# SMD_cree_driver_led-mosfet002_dem.net
KiCad netlist of a schematic drawn in EAGLE
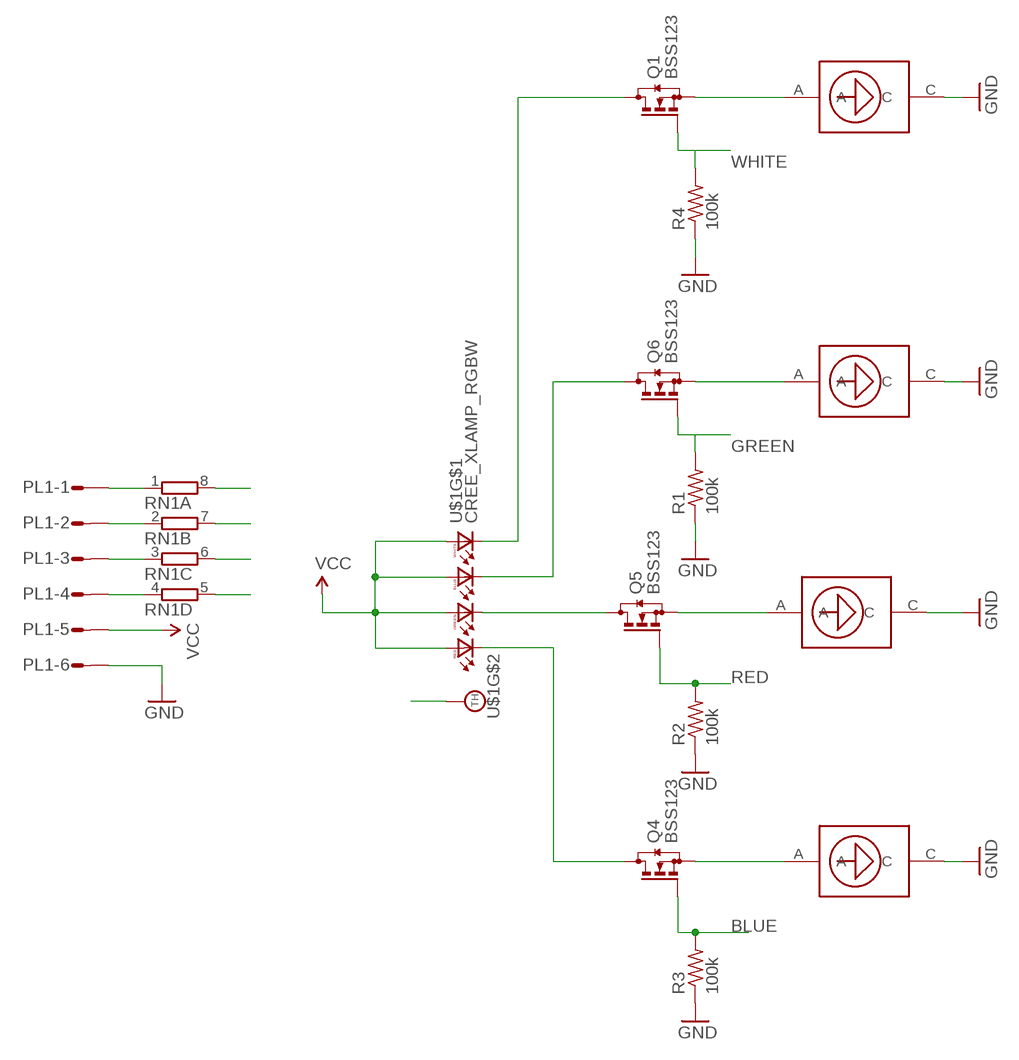
[diagram p0: schematic, sheet 1]

(export (version "E")
  (design (tool "Eeschema 10.0.6"))
  (components
    (comp (ref "PL1")
      (value "DF3-06R")
      (footprint "eagle-import:DF3R-06")
      (libsource (lib "eagle-import") (part "DF3-06R"))
    )
    (comp (ref "Q1")
      (value "BSS123")
      (footprint "eagle-import:SOT23")
      (libsource (lib "eagle-import") (part "BSS123"))
    )
    (comp (ref "Q4")
      (value "BSS123")
      (footprint "eagle-import:SOT23")
      (libsource (lib "eagle-import") (part "BSS123"))
    )
    (comp (ref "Q5")
      (value "BSS123")
      (footprint "eagle-import:SOT23")
      (libsource (lib "eagle-import") (part "BSS123"))
    )
    (comp (ref "Q6")
      (value "BSS123")
      (footprint "eagle-import:SOT23")
      (libsource (lib "eagle-import") (part "BSS123"))
    )
    (comp (ref "R1")
      (value "100k")
      (footprint "eagle-import:R0402")
      (libsource (lib "eagle-import") (part "R-US_R0402"))
    )
    (comp (ref "R2")
      (value "100k")
      (footprint "eagle-import:R0402")
      (libsource (lib "eagle-import") (part "R-US_R0402"))
    )
    (comp (ref "R3")
      (value "100k")
      (footprint "eagle-import:R0402")
      (libsource (lib "eagle-import") (part "R-US_R0402"))
    )
    (comp (ref "R4")
      (value "100k")
      (footprint "eagle-import:R0402")
      (libsource (lib "eagle-import") (part "R-US_R0402"))
    )
    (comp (ref "RN1")
      (value "4R-N0603-ARC")
      (footprint "eagle-import:0603-ARC")
      (libsource (lib "eagle-import") (part "4R-N0603-ARC"))
    )
    (comp (ref "U$1")
      (value "CREE_XLAMP_RGBW")
      (footprint "eagle-import:CREE_XLAMP_XML")
      (libsource (lib "eagle-import") (part "CREE_XLAMP_RGBW"))
    )
    (comp (ref "U$2")
      (value "NSI50350AST3G")
      (footprint "eagle-import:SMC-2")
      (libsource (lib "eagle-import") (part "NSI50350AST3G"))
    )
    (comp (ref "U$3")
      (value "NSI50350AST3G")
      (footprint "eagle-import:SMC-2")
      (libsource (lib "eagle-import") (part "NSI50350AST3G"))
    )
    (comp (ref "U$4")
      (value "NSI50350AST3G")
      (footprint "eagle-import:SMC-2")
      (libsource (lib "eagle-import") (part "NSI50350AST3G"))
    )
    (comp (ref "U$5")
      (value "NSI50350AST3G")
      (footprint "eagle-import:SMC-2")
      (libsource (lib "eagle-import") (part "NSI50350AST3G"))
    )
  )
  (nets
    (net (code "1") (name "/BLUE") (class "Default")
      (node (ref "Q4") (pin "1") (pinfunction "G_1") (pintype "passive"))
      (node (ref "R3") (pin "2") (pinfunction "2_2") (pintype "passive"))
      (node (ref "RN1") (pin "7") (pinfunction "2_7") (pintype "passive"))
    )
    (net (code "2") (name "/GREEN") (class "Default")
      (node (ref "Q6") (pin "1") (pinfunction "G_1") (pintype "passive"))
      (node (ref "R1") (pin "2") (pinfunction "2_2") (pintype "passive"))
      (node (ref "RN1") (pin "6") (pinfunction "2_6") (pintype "passive"))
    )
    (net (code "3") (name "/RED") (class "Default")
      (node (ref "Q5") (pin "1") (pinfunction "G_1") (pintype "passive"))
      (node (ref "R2") (pin "2") (pinfunction "2_2") (pintype "passive"))
      (node (ref "RN1") (pin "5") (pinfunction "2_5") (pintype "passive"))
    )
    (net (code "4") (name "/WHITE") (class "Default")
      (node (ref "Q1") (pin "1") (pinfunction "G_1") (pintype "passive"))
      (node (ref "R4") (pin "2") (pinfunction "2_2") (pintype "passive"))
      (node (ref "RN1") (pin "8") (pinfunction "2_8") (pintype "passive"))
    )
    (net (code "5") (name "GND") (class "Default")
      (node (ref "PL1") (pin "6") (pinfunction "S_6") (pintype "passive"))
      (node (ref "R1") (pin "1") (pinfunction "1_1") (pintype "passive"))
      (node (ref "R2") (pin "1") (pinfunction "1_1") (pintype "passive"))
      (node (ref "R3") (pin "1") (pinfunction "1_1") (pintype "passive"))
      (node (ref "R4") (pin "1") (pinfunction "1_1") (pintype "passive"))
      (node (ref "U$2") (pin "C") (pinfunction "C_C") (pintype "bidirectional"))
      (node (ref "U$3") (pin "C") (pinfunction "C_C") (pintype "bidirectional"))
      (node (ref "U$4") (pin "C") (pinfunction "C_C") (pintype "bidirectional"))
      (node (ref "U$5") (pin "C") (pinfunction "C_C") (pintype "bidirectional"))
    )
    (net (code "6") (name "Net-(PL1A-S)") (class "Default")
      (node (ref "PL1") (pin "1") (pinfunction "S_1") (pintype "passive"))
      (node (ref "RN1") (pin "1") (pinfunction "1_1") (pintype "passive"))
    )
    (net (code "7") (name "Net-(PL1B-S)") (class "Default")
      (node (ref "PL1") (pin "2") (pinfunction "S_2") (pintype "passive"))
      (node (ref "RN1") (pin "2") (pinfunction "1_2") (pintype "passive"))
    )
    (net (code "8") (name "Net-(PL1C-S)") (class "Default")
      (node (ref "PL1") (pin "3") (pinfunction "S_3") (pintype "passive"))
      (node (ref "RN1") (pin "3") (pinfunction "1_3") (pintype "passive"))
    )
    (net (code "9") (name "Net-(PL1D-S)") (class "Default")
      (node (ref "PL1") (pin "4") (pinfunction "S_4") (pintype "passive"))
      (node (ref "RN1") (pin "4") (pinfunction "1_4") (pintype "passive"))
    )
    (net (code "10") (name "Net-(Q1-D)") (class "Default")
      (node (ref "Q1") (pin "3") (pinfunction "D_3") (pintype "passive"))
      (node (ref "U$1") (pin "5") (pinfunction "WC_5") (pintype "passive"))
    )
    (net (code "11") (name "Net-(Q1-S)") (class "Default")
      (node (ref "Q1") (pin "2") (pinfunction "S_2") (pintype "passive"))
      (node (ref "U$5") (pin "A") (pinfunction "A_A") (pintype "bidirectional"))
    )
    (net (code "12") (name "Net-(Q4-D)") (class "Default")
      (node (ref "Q4") (pin "3") (pinfunction "D_3") (pintype "passive"))
      (node (ref "U$1") (pin "8") (pinfunction "RC_8") (pintype "passive"))
    )
    (net (code "13") (name "Net-(Q4-S)") (class "Default")
      (node (ref "Q4") (pin "2") (pinfunction "S_2") (pintype "passive"))
      (node (ref "U$4") (pin "A") (pinfunction "A_A") (pintype "bidirectional"))
    )
    (net (code "14") (name "Net-(Q5-D)") (class "Default")
      (node (ref "Q5") (pin "3") (pinfunction "D_3") (pintype "passive"))
      (node (ref "U$1") (pin "7") (pinfunction "GC_7") (pintype "passive"))
    )
    (net (code "15") (name "Net-(Q5-S)") (class "Default")
      (node (ref "Q5") (pin "2") (pinfunction "S_2") (pintype "passive"))
      (node (ref "U$3") (pin "A") (pinfunction "A_A") (pintype "bidirectional"))
    )
    (net (code "16") (name "Net-(Q6-D)") (class "Default")
      (node (ref "Q6") (pin "3") (pinfunction "D_3") (pintype "passive"))
      (node (ref "U$1") (pin "6") (pinfunction "BC_6") (pintype "passive"))
    )
    (net (code "17") (name "Net-(Q6-S)") (class "Default")
      (node (ref "Q6") (pin "2") (pinfunction "S_2") (pintype "passive"))
      (node (ref "U$2") (pin "A") (pinfunction "A_A") (pintype "bidirectional"))
    )
    (net (code "18") (name "VCC") (class "Default")
      (node (ref "PL1") (pin "5") (pinfunction "S_5") (pintype "passive"))
      (node (ref "U$1") (pin "1") (pinfunction "RA_1") (pintype "passive"))
      (node (ref "U$1") (pin "2") (pinfunction "GA_2") (pintype "passive"))
      (node (ref "U$1") (pin "3") (pinfunction "BA_3") (pintype "passive"))
      (node (ref "U$1") (pin "4") (pinfunction "WA_4") (pintype "passive"))
    )
    (net (code "19") (name "unconnected-(U$1B-TH-PadP$1)") (class "Default")
      (node (ref "U$1") (pin "P$1") (pinfunction "TH_P$1") (pintype "passive"))
    )
  )
)
